# Logic_Module_-_Power_V8.net
KiCad netlist of a schematic drawn in EAGLE
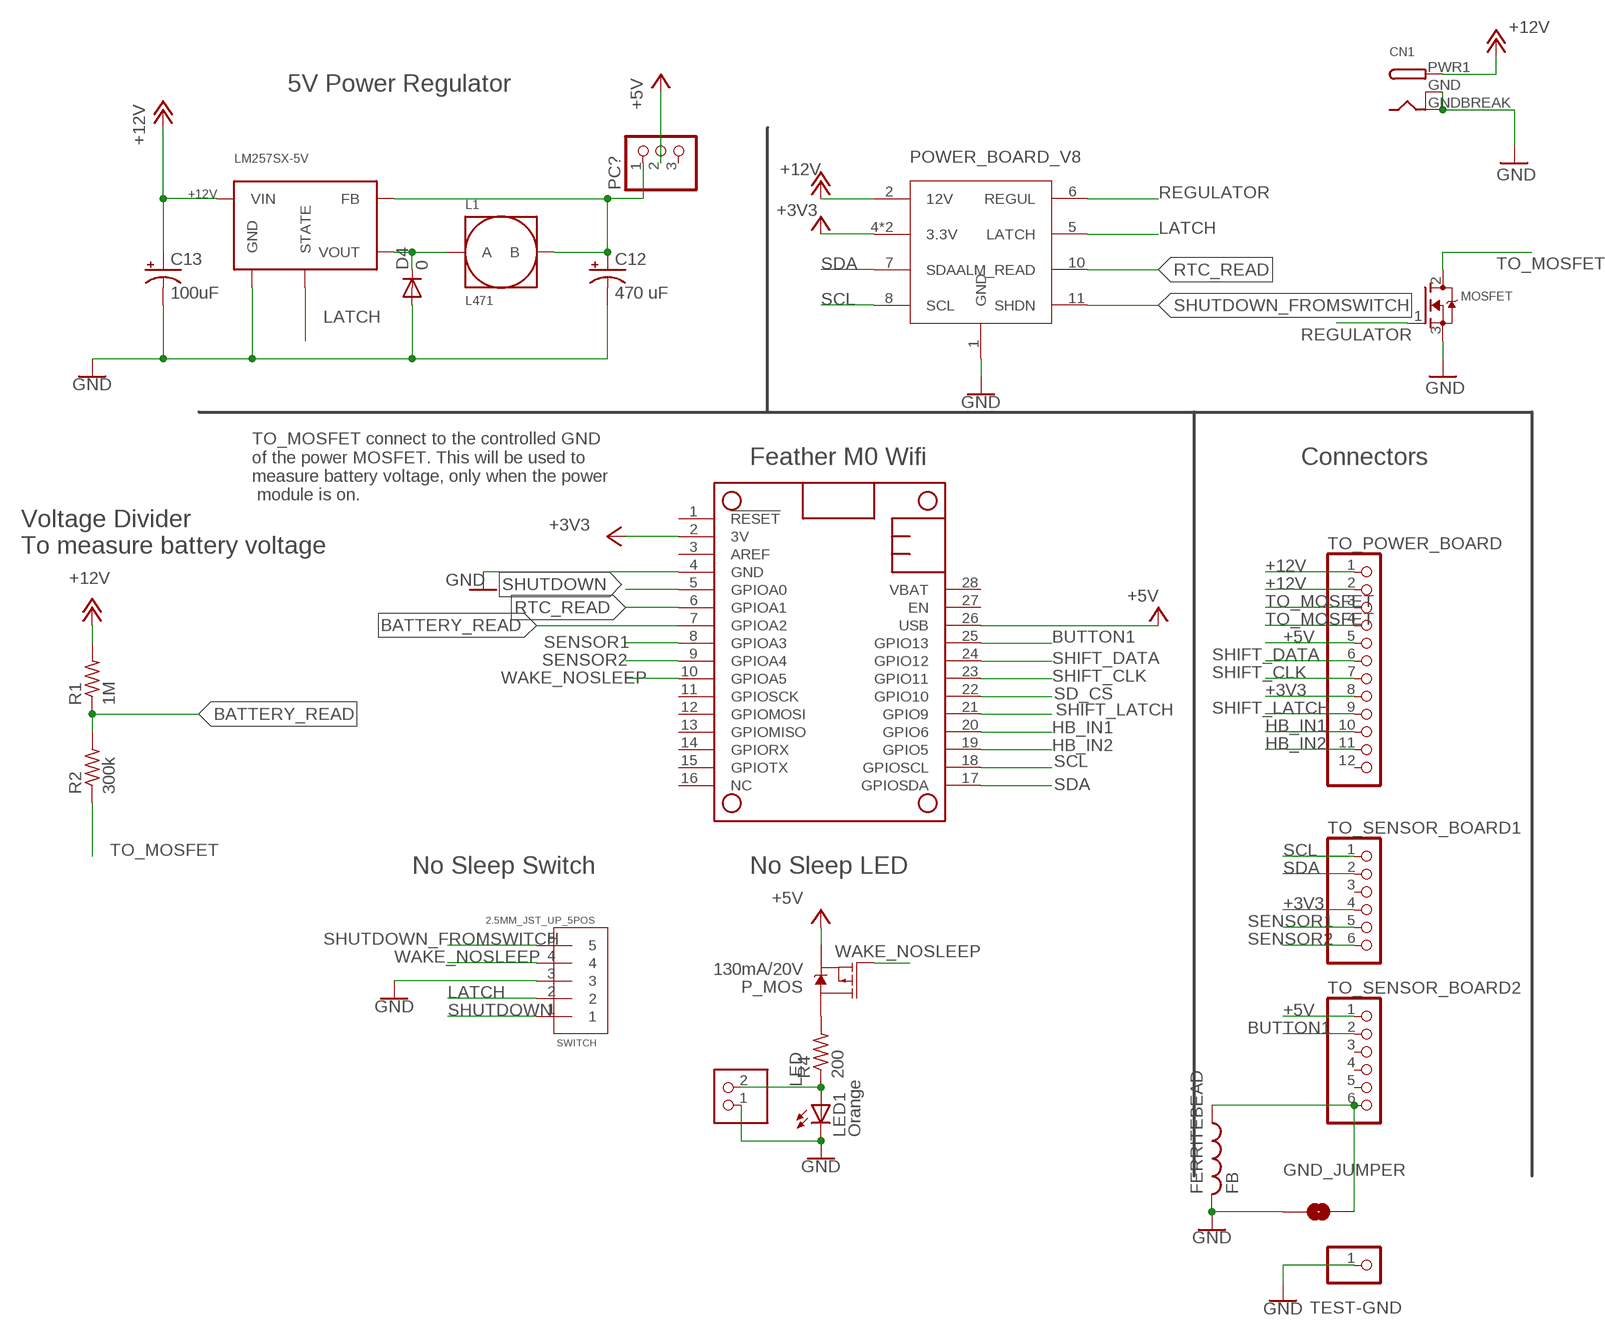
[diagram p0: schematic, sheet 1]

(export (version "E")
  (design (tool "Eeschema 10.0.6"))
  (components
    (comp (ref "C12")
      (value "470 uF")
      (footprint "eagle-import:153CLV-0810")
      (libsource (lib "eagle-import") (part "CPOL-US153CLV-0810"))
    )
    (comp (ref "C13")
      (value "100uF")
      (footprint "eagle-import:153CLV-0605")
      (libsource (lib "eagle-import") (part "CPOL-US153CLV-0605"))
    )
    (comp (ref "CN1")
      (value "DCBARRELSMT")
      (footprint "eagle-import:DCJACK_2MM_SMT")
      (libsource (lib "eagle-import") (part "DCBARRELSMT"))
    )
    (comp (ref "D4")
      (value "0")
      (footprint "eagle-import:DO41-10")
      (libsource (lib "eagle-import") (part "1N4004"))
    )
    (comp (ref "FERRITEBEAD")
      (value "FB")
      (footprint "eagle-import:FB")
      (libsource (lib "eagle-import") (part "FB"))
    )
    (comp (ref "GND_JUMPER")
      (value "JUMPER-SMT_2_NO_NO-SILK")
      (footprint "eagle-import:SMT-JUMPER_2_NO_NO-SILK")
      (libsource (lib "eagle-import") (part "JUMPER-SMT_2_NO_NO-SILK"))
    )
    (comp (ref "L1")
      (value "L471")
      (footprint "eagle-import:12-12")
      (libsource (lib "eagle-import") (part "L471"))
    )
    (comp (ref "LED")
      (value "2.5MM_JST_UP_2POS")
      (footprint "eagle-import:JST_2POS_2.5MM_UP")
      (libsource (lib "eagle-import") (part "2.5MM_JST_UP_2POS"))
    )
    (comp (ref "LED1")
      (value "Orange")
      (footprint "eagle-import:LED3MM")
      (libsource (lib "eagle-import") (part "LED3MM"))
    )
    (comp (ref "LM257SX-5V")
      (value "LM2575")
      (footprint "eagle-import:TO-263")
      (libsource (lib "eagle-import") (part "LM2575"))
    )
    (comp (ref "MOSFET")
      (value "MOSFET-NGDS_TO220V")
      (footprint "eagle-import:TO220V")
      (libsource (lib "eagle-import") (part "MOSFET-NGDS_TO220V"))
    )
    (comp (ref "MS1")
      (value "FEATHERWING")
      (footprint "eagle-import:FEATHERWING")
      (libsource (lib "eagle-import") (part "FEATHERWING"))
    )
    (comp (ref "PC?")
      (value "PINHD-1X3")
      (footprint "eagle-import:1X03")
      (libsource (lib "eagle-import") (part "PINHD-1X3"))
    )
    (comp (ref "POWER_BOARD_V8")
      (value "OPENS_POWER_8")
      (footprint "eagle-import:OPEN_POWER_8")
      (libsource (lib "eagle-import") (part "OPENS_POWER_8"))
    )
    (comp (ref "P_MOS")
      (value "130mA/20V")
      (footprint "eagle-import:SOT23-3")
      (libsource (lib "eagle-import") (part "MOSFET_PCH-IRLML2244"))
    )
    (comp (ref "R1")
      (value "1M")
      (footprint "eagle-import:R1206")
      (libsource (lib "eagle-import") (part "R-US_R1206"))
    )
    (comp (ref "R2")
      (value "300k")
      (footprint "eagle-import:R1206")
      (libsource (lib "eagle-import") (part "R-US_R1206"))
    )
    (comp (ref "R4")
      (value "200")
      (footprint "eagle-import:0204_7")
      (libsource (lib "eagle-import") (part "R-US_0204/7"))
    )
    (comp (ref "SWITCH")
      (value "2.5MM_JST_UP_5POS")
      (footprint "eagle-import:JST_5POS_2.5MM_UP")
      (libsource (lib "eagle-import") (part "2.5MM_JST_UP_5POS"))
    )
    (comp (ref "TEST-GND")
      (value "PINHD-1X1")
      (footprint "eagle-import:1X01")
      (libsource (lib "eagle-import") (part "PINHD-1X1"))
    )
    (comp (ref "TO_POWER_BOARD")
      (value "PINHD-1X12")
      (footprint "eagle-import:1X12")
      (libsource (lib "eagle-import") (part "PINHD-1X12"))
    )
    (comp (ref "TO_SENSOR_BOARD1")
      (value "PINHD-1X6CB")
      (footprint "eagle-import:1X06-CLEANBIG")
      (libsource (lib "eagle-import") (part "PINHD-1X6CB"))
    )
    (comp (ref "TO_SENSOR_BOARD2")
      (value "PINHD-1X6CB")
      (footprint "eagle-import:1X06-CLEANBIG")
      (libsource (lib "eagle-import") (part "PINHD-1X6CB"))
    )
  )
  (nets
    (net (code "1") (name "+3V3") (class "Default")
      (node (ref "MS1") (pin "2") (pinfunction "3V_2") (pintype "power_in"))
      (node (ref "POWER_BOARD_V8") (pin "4") (pinfunction "3.3V_4") (pintype "bidirectional"))
      (node (ref "POWER_BOARD_V8") (pin "9") (pinfunction "3.3V_9") (pintype "bidirectional"))
      (node (ref "TO_POWER_BOARD") (pin "8") (pinfunction "8_8") (pintype "passive"))
      (node (ref "TO_SENSOR_BOARD1") (pin "4") (pinfunction "4_4") (pintype "passive"))
    )
    (net (code "2") (name "+5V") (class "Default")
      (node (ref "MS1") (pin "26") (pinfunction "USB_26") (pintype "power_in"))
      (node (ref "PC?") (pin "2") (pinfunction "2_2") (pintype "passive"))
      (node (ref "P_MOS") (pin "2") (pinfunction "S_2") (pintype "bidirectional"))
      (node (ref "TO_POWER_BOARD") (pin "5") (pinfunction "5_5") (pintype "passive"))
      (node (ref "TO_SENSOR_BOARD2") (pin "1") (pinfunction "1_1") (pintype "passive"))
    )
    (net (code "3") (name "+12V") (class "Default")
      (node (ref "C13") (pin "+") (pinfunction "+_+") (pintype "passive"))
      (node (ref "CN1") (pin "PWR1") (pinfunction "PWR_PWR1") (pintype "power_in"))
      (node (ref "LM257SX-5V") (pin "VIN") (pinfunction "VIN_VIN") (pintype "bidirectional"))
      (node (ref "POWER_BOARD_V8") (pin "2") (pinfunction "12V_2") (pintype "bidirectional"))
      (node (ref "R1") (pin "2") (pinfunction "2_2") (pintype "passive"))
      (node (ref "TO_POWER_BOARD") (pin "1") (pinfunction "1_1") (pintype "passive"))
      (node (ref "TO_POWER_BOARD") (pin "2") (pinfunction "2_2") (pintype "passive"))
    )
    (net (code "4") (name "/BUTTON1") (class "Default")
      (node (ref "MS1") (pin "25") (pinfunction "GPIO13_25") (pintype "bidirectional"))
      (node (ref "TO_SENSOR_BOARD2") (pin "2") (pinfunction "2_2") (pintype "passive"))
    )
    (net (code "5") (name "/HB_IN1") (class "Default")
      (node (ref "MS1") (pin "20") (pinfunction "GPIO6_20") (pintype "bidirectional"))
      (node (ref "TO_POWER_BOARD") (pin "10") (pinfunction "10_10") (pintype "passive"))
    )
    (net (code "6") (name "/HB_IN2") (class "Default")
      (node (ref "MS1") (pin "19") (pinfunction "GPIO5_19") (pintype "bidirectional"))
      (node (ref "TO_POWER_BOARD") (pin "11") (pinfunction "11_11") (pintype "passive"))
    )
    (net (code "7") (name "/LATCH") (class "Default")
      (node (ref "LM257SX-5V") (pin "STATE") (pinfunction "STATE_STATE") (pintype "bidirectional"))
      (node (ref "POWER_BOARD_V8") (pin "5") (pinfunction "LATCH_5") (pintype "bidirectional"))
      (node (ref "SWITCH") (pin "2") (pinfunction "2_2") (pintype "bidirectional"))
    )
    (net (code "8") (name "/REGULATOR") (class "Default")
      (node (ref "MOSFET") (pin "1") (pinfunction "G_1") (pintype "bidirectional"))
      (node (ref "POWER_BOARD_V8") (pin "6") (pinfunction "REGUL_6") (pintype "bidirectional"))
    )
    (net (code "9") (name "/SCL") (class "Default")
      (node (ref "MS1") (pin "18") (pinfunction "GPIOSCL_18") (pintype "bidirectional"))
      (node (ref "POWER_BOARD_V8") (pin "8") (pinfunction "SCL_8") (pintype "bidirectional"))
      (node (ref "TO_SENSOR_BOARD1") (pin "1") (pinfunction "1_1") (pintype "passive"))
    )
    (net (code "10") (name "/SDA") (class "Default")
      (node (ref "MS1") (pin "17") (pinfunction "GPIOSDA_17") (pintype "bidirectional"))
      (node (ref "POWER_BOARD_V8") (pin "7") (pinfunction "SDA_7") (pintype "bidirectional"))
      (node (ref "TO_SENSOR_BOARD1") (pin "2") (pinfunction "2_2") (pintype "passive"))
    )
    (net (code "11") (name "/SD_CS") (class "Default")
      (node (ref "MS1") (pin "22") (pinfunction "GPIO10_22") (pintype "bidirectional"))
    )
    (net (code "12") (name "/SENSOR1") (class "Default")
      (node (ref "MS1") (pin "8") (pinfunction "GPIOA3_8") (pintype "bidirectional"))
      (node (ref "TO_SENSOR_BOARD1") (pin "5") (pinfunction "5_5") (pintype "passive"))
    )
    (net (code "13") (name "/SENSOR2") (class "Default")
      (node (ref "MS1") (pin "9") (pinfunction "GPIOA4_9") (pintype "bidirectional"))
      (node (ref "TO_SENSOR_BOARD1") (pin "6") (pinfunction "6_6") (pintype "passive"))
    )
    (net (code "14") (name "/SHIFT_CLK") (class "Default")
      (node (ref "MS1") (pin "23") (pinfunction "GPIO11_23") (pintype "bidirectional"))
      (node (ref "TO_POWER_BOARD") (pin "7") (pinfunction "7_7") (pintype "passive"))
    )
    (net (code "15") (name "/SHIFT_DATA") (class "Default")
      (node (ref "MS1") (pin "24") (pinfunction "GPIO12_24") (pintype "bidirectional"))
      (node (ref "TO_POWER_BOARD") (pin "6") (pinfunction "6_6") (pintype "passive"))
    )
    (net (code "16") (name "/SHIFT_LATCH") (class "Default")
      (node (ref "MS1") (pin "21") (pinfunction "GPIO9_21") (pintype "bidirectional"))
      (node (ref "TO_POWER_BOARD") (pin "9") (pinfunction "9_9") (pintype "passive"))
    )
    (net (code "17") (name "/TO_MOSFET") (class "Default")
      (node (ref "MOSFET") (pin "2") (pinfunction "D_2") (pintype "bidirectional"))
      (node (ref "R2") (pin "1") (pinfunction "1_1") (pintype "passive"))
      (node (ref "TO_POWER_BOARD") (pin "3") (pinfunction "3_3") (pintype "passive"))
      (node (ref "TO_POWER_BOARD") (pin "4") (pinfunction "4_4") (pintype "passive"))
    )
    (net (code "18") (name "/VBAT") (class "Default")
      (node (ref "MS1") (pin "28") (pinfunction "VBAT_28") (pintype "power_in"))
    )
    (net (code "19") (name "/WAKE_NOSLEEP") (class "Default")
      (node (ref "MS1") (pin "10") (pinfunction "GPIOA5_10") (pintype "bidirectional"))
      (node (ref "P_MOS") (pin "1") (pinfunction "G_1") (pintype "bidirectional"))
      (node (ref "SWITCH") (pin "4") (pinfunction "4_4") (pintype "bidirectional"))
    )
    (net (code "20") (name "BATTERY_READ") (class "Default")
      (node (ref "MS1") (pin "7") (pinfunction "GPIOA2_7") (pintype "bidirectional"))
      (node (ref "R1") (pin "1") (pinfunction "1_1") (pintype "passive"))
      (node (ref "R2") (pin "2") (pinfunction "2_2") (pintype "passive"))
    )
    (net (code "21") (name "GND") (class "Default")
      (node (ref "C12") (pin "-") (pinfunction "-_-") (pintype "passive"))
      (node (ref "C13") (pin "-") (pinfunction "-_-") (pintype "passive"))
      (node (ref "CN1") (pin "GND") (pinfunction "GNDBREAK_GND") (pintype "power_in"))
      (node (ref "CN1") (pin "GNDBREAK") (pinfunction "GND_GNDBREAK") (pintype "power_in"))
      (node (ref "D4") (pin "A") (pinfunction "A_A") (pintype "passive"))
      (node (ref "FERRITEBEAD") (pin "P$2") (pinfunction "2_P$2") (pintype "passive"))
      (node (ref "GND_JUMPER") (pin "1") (pinfunction "1_1") (pintype "passive"))
      (node (ref "LED") (pin "1") (pinfunction "1_1") (pintype "bidirectional"))
      (node (ref "LED1") (pin "K") (pinfunction "C_K") (pintype "passive"))
      (node (ref "LM257SX-5V") (pin "GND") (pinfunction "GND_GND") (pintype "bidirectional"))
      (node (ref "MOSFET") (pin "3") (pinfunction "S_3") (pintype "bidirectional"))
      (node (ref "MS1") (pin "4") (pinfunction "GND_4") (pintype "power_in"))
      (node (ref "POWER_BOARD_V8") (pin "1") (pinfunction "GND_1") (pintype "bidirectional"))
      (node (ref "SWITCH") (pin "3") (pinfunction "3_3") (pintype "bidirectional"))
      (node (ref "TEST-GND") (pin "1") (pinfunction "1_1") (pintype "passive"))
    )
    (net (code "22") (name "Net-(C12-Pad+)") (class "Default")
      (node (ref "C12") (pin "+") (pinfunction "+_+") (pintype "passive"))
      (node (ref "L1") (pin "B") (pinfunction "B_B") (pintype "bidirectional"))
      (node (ref "LM257SX-5V") (pin "FB") (pinfunction "FB_FB") (pintype "bidirectional"))
      (node (ref "PC?") (pin "1") (pinfunction "1_1") (pintype "passive"))
    )
    (net (code "23") (name "Net-(D4-PadC)") (class "Default")
      (node (ref "D4") (pin "C") (pinfunction "C_C") (pintype "passive"))
      (node (ref "L1") (pin "A") (pinfunction "A_A") (pintype "bidirectional"))
      (node (ref "LM257SX-5V") (pin "VOUT") (pinfunction "VOUT_VOUT") (pintype "bidirectional"))
    )
    (net (code "24") (name "Net-(FERRITEBEAD-1)") (class "Default")
      (node (ref "FERRITEBEAD") (pin "P$1") (pinfunction "1_P$1") (pintype "passive"))
      (node (ref "GND_JUMPER") (pin "2") (pinfunction "2_2") (pintype "passive"))
      (node (ref "TO_SENSOR_BOARD2") (pin "6") (pinfunction "6_6") (pintype "passive"))
    )
    (net (code "25") (name "Net-(LED-Pad2)") (class "Default")
      (node (ref "LED") (pin "2") (pinfunction "2_2") (pintype "bidirectional"))
      (node (ref "LED1") (pin "A") (pinfunction "A_A") (pintype "passive"))
      (node (ref "R4") (pin "1") (pinfunction "1_1") (pintype "passive"))
    )
    (net (code "26") (name "Net-(P_MOS-D)") (class "Default")
      (node (ref "P_MOS") (pin "3") (pinfunction "D_3") (pintype "bidirectional"))
      (node (ref "R4") (pin "2") (pinfunction "2_2") (pintype "passive"))
    )
    (net (code "27") (name "RTC_READ") (class "Default")
      (node (ref "MS1") (pin "6") (pinfunction "GPIOA1_6") (pintype "bidirectional"))
      (node (ref "POWER_BOARD_V8") (pin "10") (pinfunction "ALM_READ_10") (pintype "bidirectional"))
    )
    (net (code "28") (name "SHUTDOWN") (class "Default")
      (node (ref "MS1") (pin "5") (pinfunction "GPIOA0_5") (pintype "bidirectional"))
      (node (ref "SWITCH") (pin "1") (pinfunction "1_1") (pintype "bidirectional"))
    )
    (net (code "29") (name "SHUTDOWN_FROMSWITCH") (class "Default")
      (node (ref "POWER_BOARD_V8") (pin "11") (pinfunction "SHDN_11") (pintype "bidirectional"))
      (node (ref "SWITCH") (pin "5") (pinfunction "5_5") (pintype "bidirectional"))
    )
    (net (code "30") (name "unconnected-(MS1-AREF-Pad3)") (class "Default")
      (node (ref "MS1") (pin "3") (pinfunction "AREF_3") (pintype "passive"))
    )
    (net (code "31") (name "unconnected-(MS1-EN-Pad27)") (class "Default")
      (node (ref "MS1") (pin "27") (pinfunction "EN_27") (pintype "passive"))
    )
    (net (code "32") (name "unconnected-(MS1-GPIOMISO-Pad13)") (class "Default")
      (node (ref "MS1") (pin "13") (pinfunction "GPIOMISO_13") (pintype "bidirectional"))
    )
    (net (code "33") (name "unconnected-(MS1-GPIOMOSI-Pad12)") (class "Default")
      (node (ref "MS1") (pin "12") (pinfunction "GPIOMOSI_12") (pintype "bidirectional"))
    )
    (net (code "34") (name "unconnected-(MS1-GPIORX-Pad14)") (class "Default")
      (node (ref "MS1") (pin "14") (pinfunction "GPIORX_14") (pintype "bidirectional"))
    )
    (net (code "35") (name "unconnected-(MS1-GPIOSCK-Pad11)") (class "Default")
      (node (ref "MS1") (pin "11") (pinfunction "GPIOSCK_11") (pintype "bidirectional"))
    )
    (net (code "36") (name "unconnected-(MS1-GPIOTX-Pad15)") (class "Default")
      (node (ref "MS1") (pin "15") (pinfunction "GPIOTX_15") (pintype "bidirectional"))
    )
    (net (code "37") (name "unconnected-(MS1-NC-Pad16)") (class "Default")
      (node (ref "MS1") (pin "16") (pinfunction "NC_16") (pintype "passive"))
    )
    (net (code "38") (name "unconnected-(MS1-~{RESET}-Pad1)") (class "Default")
      (node (ref "MS1") (pin "1") (pinfunction "~{RESET}_1") (pintype "input"))
    )
    (net (code "39") (name "unconnected-(TO_POWER_BOARD-Pad12)") (class "Default")
      (node (ref "TO_POWER_BOARD") (pin "12") (pinfunction "12_12") (pintype "passive"))
    )
    (net (code "40") (name "unconnected-(TO_SENSOR_BOARD1-Pad3)") (class "Default")
      (node (ref "TO_SENSOR_BOARD1") (pin "3") (pinfunction "3_3") (pintype "passive"))
    )
    (net (code "41") (name "unconnected-(TO_SENSOR_BOARD2-Pad3)") (class "Default")
      (node (ref "TO_SENSOR_BOARD2") (pin "3") (pinfunction "3_3") (pintype "passive"))
    )
    (net (code "42") (name "unconnected-(TO_SENSOR_BOARD2-Pad4)") (class "Default")
      (node (ref "TO_SENSOR_BOARD2") (pin "4") (pinfunction "4_4") (pintype "passive"))
    )
    (net (code "43") (name "unconnected-(TO_SENSOR_BOARD2-Pad5)") (class "Default")
      (node (ref "TO_SENSOR_BOARD2") (pin "5") (pinfunction "5_5") (pintype "passive"))
    )
  )
)
